# Rover_Interface_Board.net
KiCad netlist of a schematic drawn in EAGLE
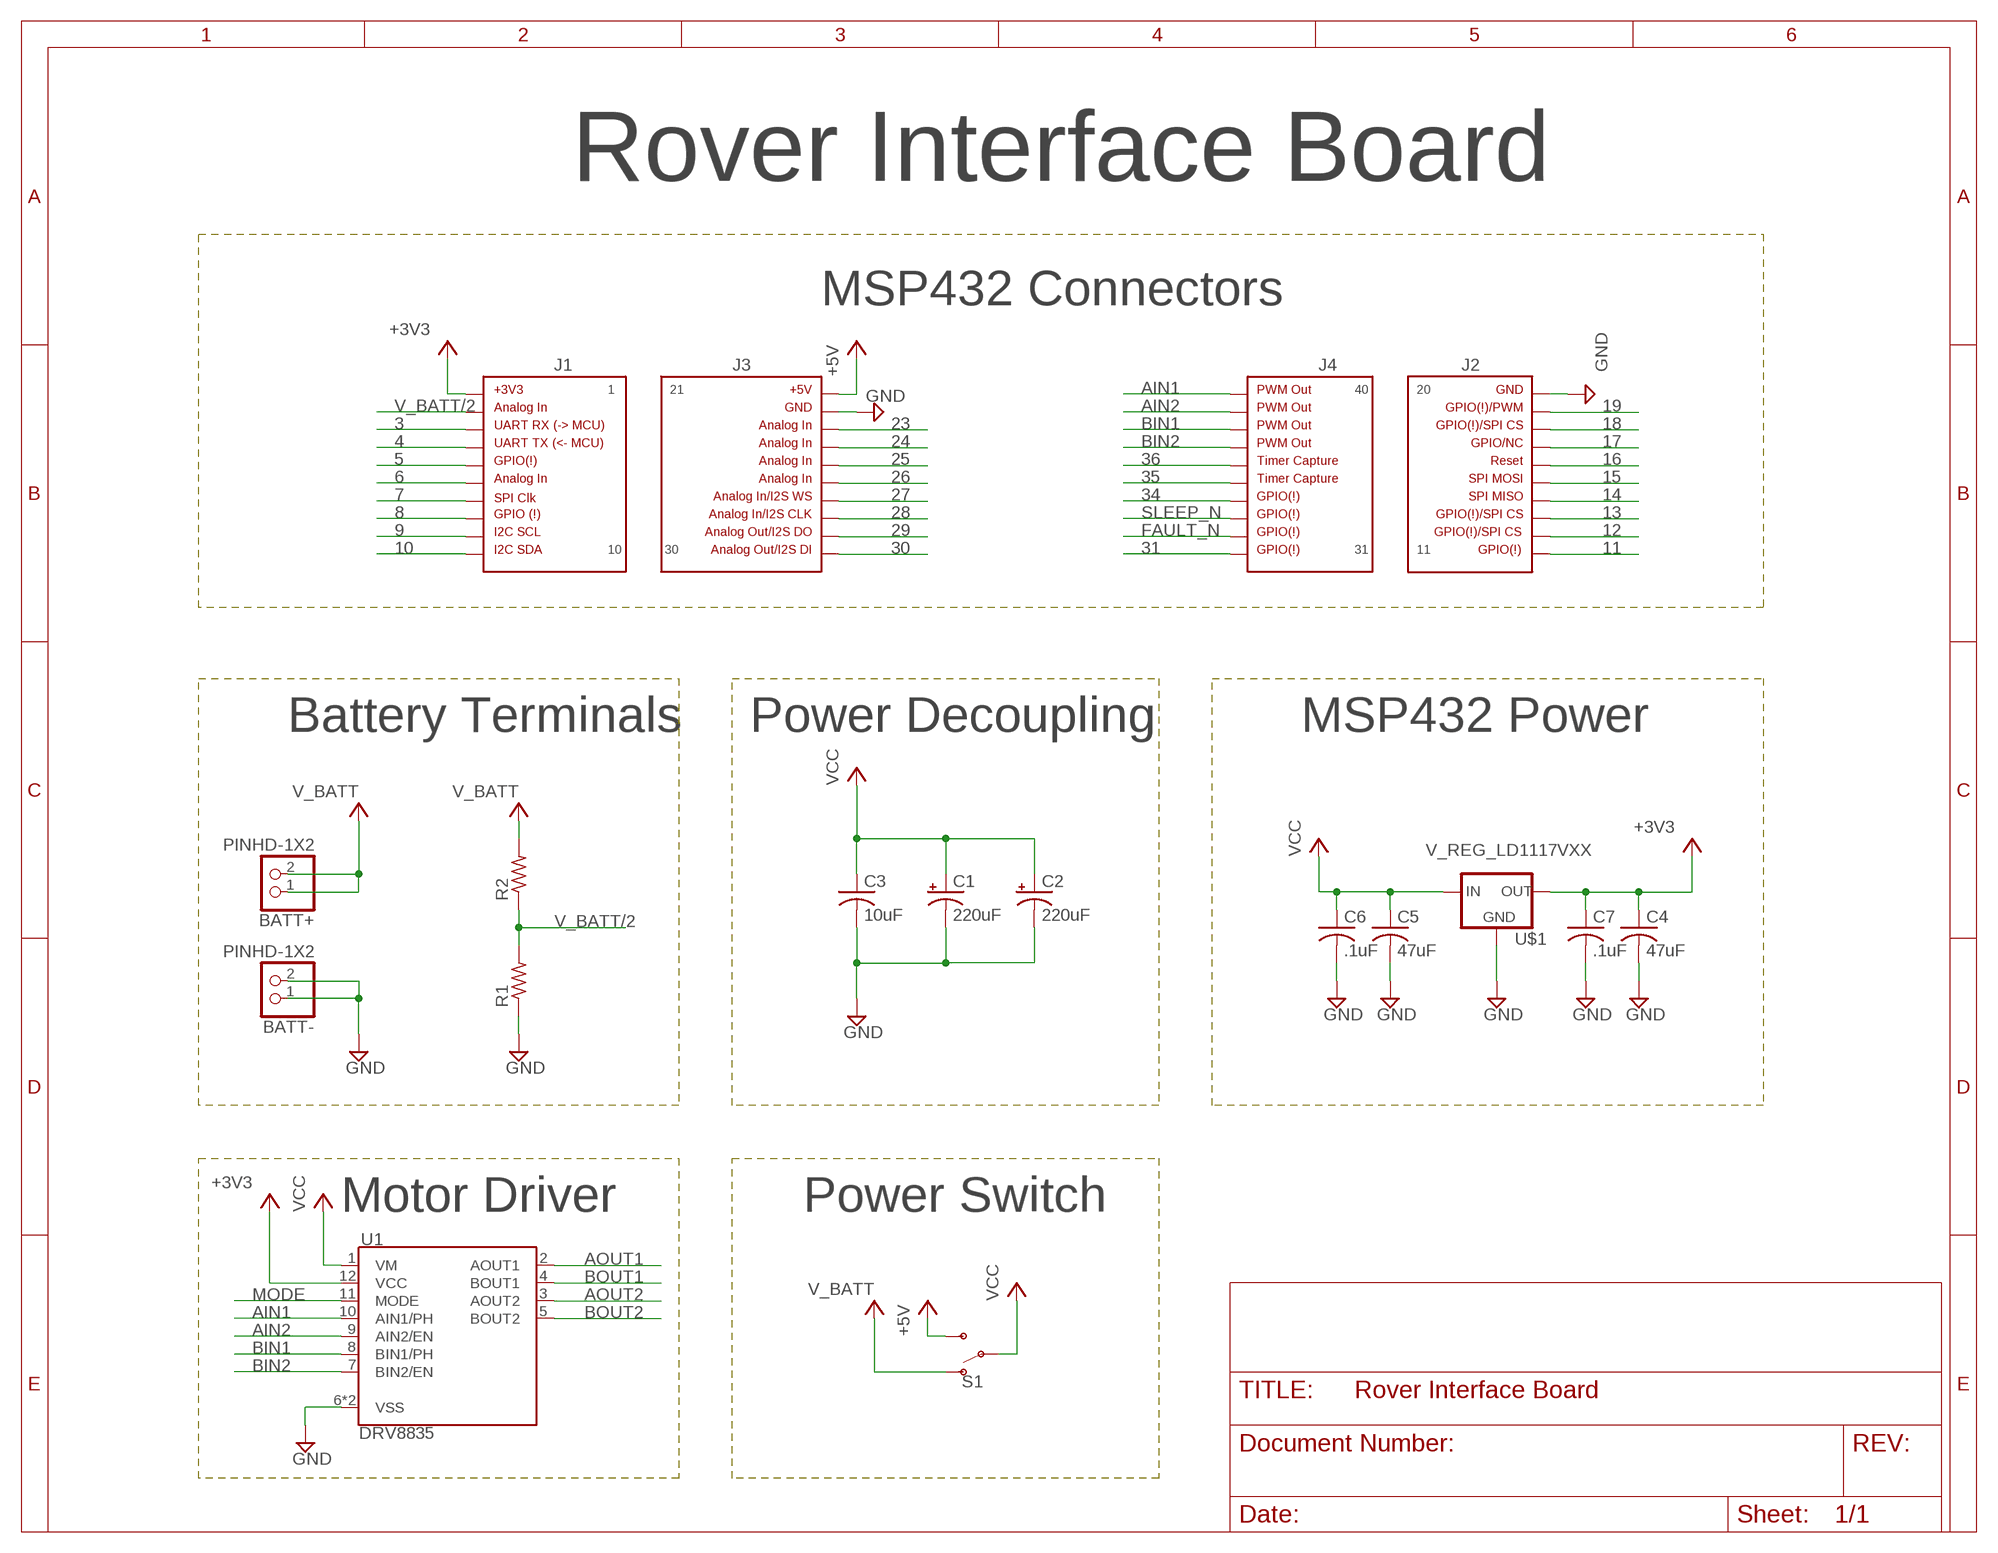
[diagram p0: schematic, sheet 1]

(export (version "E")
  (design (tool "Eeschema 10.0.6"))
  (components
    (comp (ref "BATT+")
      (value "PINHD-1X2")
      (footprint "eagle-import:1X02")
      (libsource (lib "eagle-import") (part "PINHD-1X2"))
    )
    (comp (ref "BATT-")
      (value "PINHD-1X2")
      (footprint "eagle-import:1X02")
      (libsource (lib "eagle-import") (part "PINHD-1X2"))
    )
    (comp (ref "C1")
      (value "220uF")
      (footprint "eagle-import:CPOL-RADIAL-5MM-10MM")
      (libsource (lib "eagle-import") (part "1000UF-RADIAL-5MM-25V-20%"))
    )
    (comp (ref "C2")
      (value "220uF")
      (footprint "eagle-import:CPOL-RADIAL-5MM-10MM")
      (libsource (lib "eagle-import") (part "1000UF-RADIAL-5MM-25V-20%"))
    )
    (comp (ref "C3")
      (value "10uF")
      (footprint "eagle-import:C025-050X050")
      (libsource (lib "eagle-import") (part "C-US025-050X050"))
    )
    (comp (ref "C4")
      (value "47uF")
      (footprint "eagle-import:C025-050X050")
      (libsource (lib "eagle-import") (part "C-US025-050X050"))
    )
    (comp (ref "C5")
      (value "47uF")
      (footprint "eagle-import:C025-050X050")
      (libsource (lib "eagle-import") (part "C-US025-050X050"))
    )
    (comp (ref "C6")
      (value ".1uF")
      (footprint "eagle-import:C025-050X050")
      (libsource (lib "eagle-import") (part "C-US025-050X050"))
    )
    (comp (ref "C7")
      (value ".1uF")
      (footprint "eagle-import:C025-050X050")
      (libsource (lib "eagle-import") (part "C-US025-050X050"))
    )
    (comp (ref "J1")
      (value "HEADER1X10-J1SILK_LABELS")
      (footprint "eagle-import:J1")
      (libsource (lib "eagle-import") (part "HEADER1X10-J1SILK_LABELS"))
    )
    (comp (ref "J2")
      (value "HEADER1X10-J2SILK_LABELS")
      (footprint "eagle-import:J2")
      (libsource (lib "eagle-import") (part "HEADER1X10-J2SILK_LABELS"))
    )
    (comp (ref "J3")
      (value "HEADER1X10-J3")
      (footprint "eagle-import:J3")
      (libsource (lib "eagle-import") (part "HEADER1X10-J3"))
    )
    (comp (ref "J4")
      (value "HEADER1X10-J4SILK_LABELS")
      (footprint "eagle-import:J4")
      (libsource (lib "eagle-import") (part "HEADER1X10-J4SILK_LABELS"))
    )
    (comp (ref "R1")
      (value "R-US_0204/7")
      (footprint "eagle-import:0204_7")
      (libsource (lib "eagle-import") (part "R-US_0204/7"))
    )
    (comp (ref "R2")
      (value "R-US_0204/7")
      (footprint "eagle-import:0204_7")
      (libsource (lib "eagle-import") (part "R-US_0204/7"))
    )
    (comp (ref "S1")
      (value "SWITCH-SPDT-PTH-11.6X4.0MM")
      (footprint "eagle-import:SWITCH_SPDT_PTH_11.6X4.0MM")
      (libsource (lib "eagle-import") (part "SWITCH-SPDT-PTH-11.6X4.0MM"))
    )
    (comp (ref "U$1")
      (value "V_REG_LD1117VXX")
      (footprint "eagle-import:78XXL")
      (libsource (lib "eagle-import") (part "V_REG_LD1117VXX"))
    )
    (comp (ref "U1")
      (value "DRV8835")
      (footprint "eagle-import:WSON-12")
      (libsource (lib "eagle-import") (part "DRV883X"))
    )
  )
  (nets
    (net (code "1") (name "+3V3") (class "Default")
      (node (ref "C4") (pin "1") (pinfunction "1_1") (pintype "passive"))
      (node (ref "C7") (pin "1") (pinfunction "1_1") (pintype "passive"))
      (node (ref "J1") (pin "1") (pinfunction "1_1") (pintype "bidirectional"))
      (node (ref "U$1") (pin "GND") (pinfunction "OUT_GND") (pintype "passive"))
      (node (ref "U1") (pin "12") (pinfunction "VCC_12") (pintype "bidirectional"))
    )
    (net (code "2") (name "+5V") (class "Default")
      (node (ref "J3") (pin "21") (pinfunction "21_21") (pintype "bidirectional"))
      (node (ref "S1") (pin "3") (pinfunction "S_3") (pintype "passive"))
    )
    (net (code "3") (name "/3") (class "Default")
      (node (ref "J1") (pin "3") (pinfunction "3_3") (pintype "bidirectional"))
    )
    (net (code "4") (name "/4") (class "Default")
      (node (ref "J1") (pin "4") (pinfunction "4_4") (pintype "bidirectional"))
    )
    (net (code "5") (name "/5") (class "Default")
      (node (ref "J1") (pin "5") (pinfunction "5_5") (pintype "bidirectional"))
    )
    (net (code "6") (name "/6") (class "Default")
      (node (ref "J1") (pin "6") (pinfunction "6_6") (pintype "bidirectional"))
    )
    (net (code "7") (name "/7") (class "Default")
      (node (ref "J1") (pin "7") (pinfunction "7_7") (pintype "bidirectional"))
    )
    (net (code "8") (name "/8") (class "Default")
      (node (ref "J1") (pin "8") (pinfunction "8_8") (pintype "bidirectional"))
    )
    (net (code "9") (name "/9") (class "Default")
      (node (ref "J1") (pin "9") (pinfunction "9_9") (pintype "bidirectional"))
    )
    (net (code "10") (name "/10") (class "Default")
      (node (ref "J1") (pin "10") (pinfunction "10_10") (pintype "bidirectional"))
    )
    (net (code "11") (name "/11") (class "Default")
      (node (ref "J2") (pin "11") (pinfunction "11_11") (pintype "bidirectional"))
    )
    (net (code "12") (name "/12") (class "Default")
      (node (ref "J2") (pin "12") (pinfunction "12_12") (pintype "bidirectional"))
    )
    (net (code "13") (name "/13") (class "Default")
      (node (ref "J2") (pin "13") (pinfunction "13_13") (pintype "bidirectional"))
    )
    (net (code "14") (name "/14") (class "Default")
      (node (ref "J2") (pin "14") (pinfunction "14_14") (pintype "bidirectional"))
    )
    (net (code "15") (name "/15") (class "Default")
      (node (ref "J2") (pin "15") (pinfunction "15_15") (pintype "bidirectional"))
    )
    (net (code "16") (name "/16") (class "Default")
      (node (ref "J2") (pin "16") (pinfunction "16_16") (pintype "bidirectional"))
    )
    (net (code "17") (name "/17") (class "Default")
      (node (ref "J2") (pin "17") (pinfunction "17_17") (pintype "bidirectional"))
    )
    (net (code "18") (name "/18") (class "Default")
      (node (ref "J2") (pin "18") (pinfunction "18_18") (pintype "bidirectional"))
    )
    (net (code "19") (name "/19") (class "Default")
      (node (ref "J2") (pin "19") (pinfunction "19_19") (pintype "bidirectional"))
    )
    (net (code "20") (name "/23") (class "Default")
      (node (ref "J3") (pin "23") (pinfunction "23_23") (pintype "bidirectional"))
    )
    (net (code "21") (name "/24") (class "Default")
      (node (ref "J3") (pin "24") (pinfunction "24_24") (pintype "bidirectional"))
    )
    (net (code "22") (name "/25") (class "Default")
      (node (ref "J3") (pin "25") (pinfunction "25_25") (pintype "bidirectional"))
    )
    (net (code "23") (name "/26") (class "Default")
      (node (ref "J3") (pin "26") (pinfunction "26_26") (pintype "bidirectional"))
    )
    (net (code "24") (name "/27") (class "Default")
      (node (ref "J3") (pin "27") (pinfunction "27_27") (pintype "bidirectional"))
    )
    (net (code "25") (name "/28") (class "Default")
      (node (ref "J3") (pin "28") (pinfunction "28_28") (pintype "bidirectional"))
    )
    (net (code "26") (name "/29") (class "Default")
      (node (ref "J3") (pin "29") (pinfunction "29_29") (pintype "bidirectional"))
    )
    (net (code "27") (name "/30") (class "Default")
      (node (ref "J3") (pin "30") (pinfunction "30_30") (pintype "bidirectional"))
    )
    (net (code "28") (name "/31") (class "Default")
      (node (ref "J4") (pin "31") (pinfunction "31_31") (pintype "bidirectional"))
    )
    (net (code "29") (name "/34") (class "Default")
      (node (ref "J4") (pin "34") (pinfunction "34_34") (pintype "bidirectional"))
    )
    (net (code "30") (name "/35") (class "Default")
      (node (ref "J4") (pin "35") (pinfunction "35_35") (pintype "bidirectional"))
    )
    (net (code "31") (name "/36") (class "Default")
      (node (ref "J4") (pin "36") (pinfunction "36_36") (pintype "bidirectional"))
    )
    (net (code "32") (name "/AIN1") (class "Default")
      (node (ref "J4") (pin "40") (pinfunction "40_40") (pintype "bidirectional"))
      (node (ref "U1") (pin "10") (pinfunction "AIN1/PH_10") (pintype "bidirectional"))
    )
    (net (code "33") (name "/AIN2") (class "Default")
      (node (ref "J4") (pin "39") (pinfunction "39_39") (pintype "bidirectional"))
      (node (ref "U1") (pin "9") (pinfunction "AIN2/EN_9") (pintype "bidirectional"))
    )
    (net (code "34") (name "/AOUT1") (class "Default")
      (node (ref "U1") (pin "2") (pinfunction "AOUT1_2") (pintype "bidirectional"))
    )
    (net (code "35") (name "/AOUT2") (class "Default")
      (node (ref "U1") (pin "3") (pinfunction "AOUT2_3") (pintype "bidirectional"))
    )
    (net (code "36") (name "/BIN1") (class "Default")
      (node (ref "J4") (pin "38") (pinfunction "38_38") (pintype "bidirectional"))
      (node (ref "U1") (pin "8") (pinfunction "BIN1/PH_8") (pintype "bidirectional"))
    )
    (net (code "37") (name "/BIN2") (class "Default")
      (node (ref "J4") (pin "37") (pinfunction "37_37") (pintype "bidirectional"))
      (node (ref "U1") (pin "7") (pinfunction "BIN2/EN_7") (pintype "bidirectional"))
    )
    (net (code "38") (name "/BOUT1") (class "Default")
      (node (ref "U1") (pin "4") (pinfunction "BOUT1_4") (pintype "bidirectional"))
    )
    (net (code "39") (name "/BOUT2") (class "Default")
      (node (ref "U1") (pin "5") (pinfunction "BOUT2_5") (pintype "bidirectional"))
    )
    (net (code "40") (name "/FAULT_N") (class "Default")
      (node (ref "J4") (pin "32") (pinfunction "32_32") (pintype "bidirectional"))
    )
    (net (code "41") (name "/MODE") (class "Default")
      (node (ref "U1") (pin "11") (pinfunction "MODE_11") (pintype "bidirectional"))
    )
    (net (code "42") (name "/SLEEP_N") (class "Default")
      (node (ref "J4") (pin "33") (pinfunction "33_33") (pintype "bidirectional"))
    )
    (net (code "43") (name "/V_BATT{slash}2") (class "Default")
      (node (ref "J1") (pin "2") (pinfunction "2_2") (pintype "bidirectional"))
      (node (ref "R1") (pin "2") (pinfunction "2_2") (pintype "passive"))
      (node (ref "R2") (pin "1") (pinfunction "1_1") (pintype "passive"))
    )
    (net (code "44") (name "GND") (class "Default")
      (node (ref "BATT-") (pin "1") (pinfunction "1_1") (pintype "passive"))
      (node (ref "BATT-") (pin "2") (pinfunction "2_2") (pintype "passive"))
      (node (ref "C1") (pin "-") (pinfunction "-_-") (pintype "passive"))
      (node (ref "C2") (pin "-") (pinfunction "-_-") (pintype "passive"))
      (node (ref "C3") (pin "2") (pinfunction "2_2") (pintype "passive"))
      (node (ref "C4") (pin "2") (pinfunction "2_2") (pintype "passive"))
      (node (ref "C5") (pin "2") (pinfunction "2_2") (pintype "passive"))
      (node (ref "C6") (pin "2") (pinfunction "2_2") (pintype "passive"))
      (node (ref "C7") (pin "2") (pinfunction "2_2") (pintype "passive"))
      (node (ref "J2") (pin "20") (pinfunction "20_20") (pintype "bidirectional"))
      (node (ref "J3") (pin "22") (pinfunction "22_22") (pintype "bidirectional"))
      (node (ref "R1") (pin "1") (pinfunction "1_1") (pintype "passive"))
      (node (ref "U$1") (pin "IN") (pinfunction "GND_IN") (pintype "input"))
      (node (ref "U1") (pin "6") (pinfunction "VSS_6") (pintype "bidirectional"))
      (node (ref "U1") (pin "PAD") (pinfunction "VSS_PAD") (pintype "bidirectional"))
    )
    (net (code "45") (name "VCC") (class "Default")
      (node (ref "C1") (pin "+") (pinfunction "+_+") (pintype "passive"))
      (node (ref "C2") (pin "+") (pinfunction "+_+") (pintype "passive"))
      (node (ref "C3") (pin "1") (pinfunction "1_1") (pintype "passive"))
      (node (ref "C5") (pin "1") (pinfunction "1_1") (pintype "passive"))
      (node (ref "C6") (pin "1") (pinfunction "1_1") (pintype "passive"))
      (node (ref "S1") (pin "2") (pinfunction "P_2") (pintype "passive"))
      (node (ref "U$1") (pin "OUT") (pinfunction "IN_OUT") (pintype "input"))
      (node (ref "U1") (pin "1") (pinfunction "VM_1") (pintype "bidirectional"))
    )
    (net (code "46") (name "V_BATT") (class "Default")
      (node (ref "BATT+") (pin "1") (pinfunction "1_1") (pintype "passive"))
      (node (ref "BATT+") (pin "2") (pinfunction "2_2") (pintype "passive"))
      (node (ref "R2") (pin "2") (pinfunction "2_2") (pintype "passive"))
      (node (ref "S1") (pin "1") (pinfunction "O_1") (pintype "passive"))
    )
  )
)
